# Buzzer.net
KiCad netlist of a schematic drawn in EAGLE
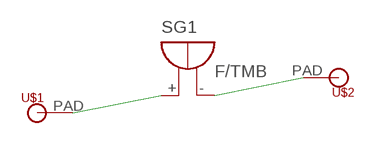
[diagram p0: schematic, sheet 1]

(export (version "E")
  (design (tool "Eeschema 10.0.6"))
  (components
    (comp (ref "SG1")
      (value "F/TMB")
      (footprint "eagle-import:F_TMB")
      (libsource (lib "eagle-import") (part "F/TMB"))
    )
    (comp (ref "U$1")
      (value "MICROBIT_PAD")
      (footprint "eagle-import:MICROBIT_PAD")
      (libsource (lib "eagle-import") (part "MICROBIT_PAD"))
    )
    (comp (ref "U$2")
      (value "MICROBIT_PAD")
      (footprint "eagle-import:MICROBIT_PAD")
      (libsource (lib "eagle-import") (part "MICROBIT_PAD"))
    )
  )
  (nets
    (net (code "1") (name "Net-(U$1-P$1)") (class "Default")
      (node (ref "SG1") (pin "+") (pinfunction "+_+") (pintype "passive"))
      (node (ref "U$1") (pin "PAD") (pinfunction "P$1_PAD") (pintype "bidirectional"))
    )
    (net (code "2") (name "Net-(U$2-P$1)") (class "Default")
      (node (ref "SG1") (pin "-") (pinfunction "-_-") (pintype "passive"))
      (node (ref "U$2") (pin "PAD") (pinfunction "P$1_PAD") (pintype "bidirectional"))
    )
  )
)
